# esp8266-somfy-switching.net
KiCad netlist of a schematic drawn in EAGLE
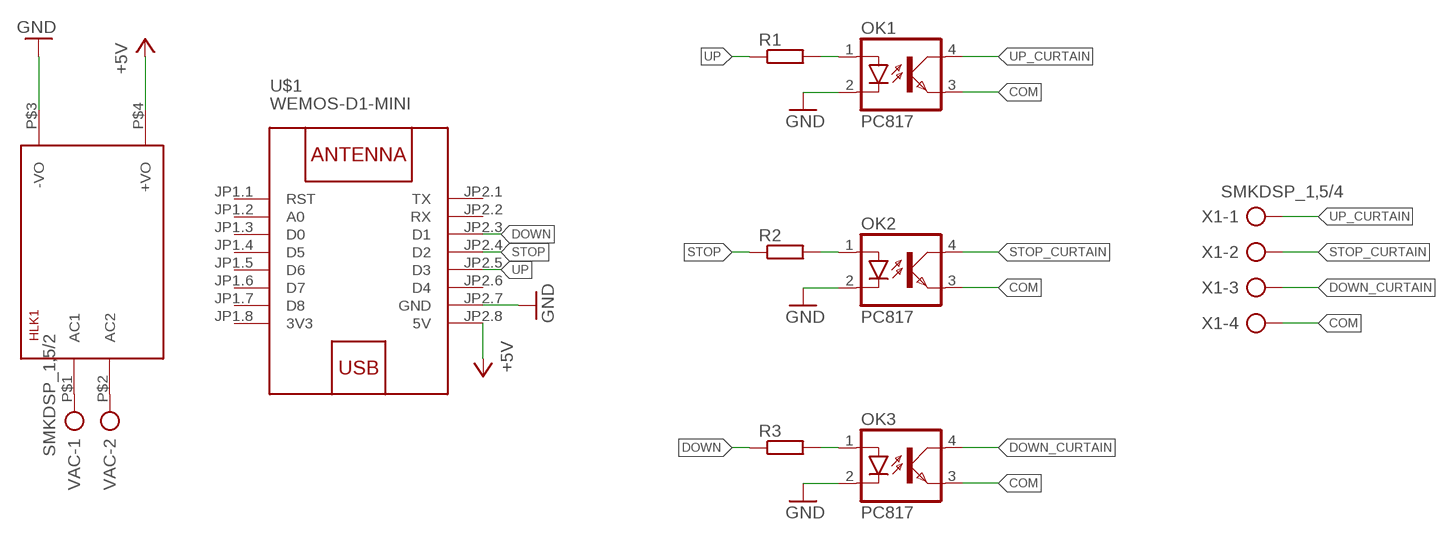
[diagram p0: schematic, sheet 1]

(export (version "E")
  (design (tool "Eeschema 10.0.6"))
  (components
    (comp (ref "HLK1")
      (value "HLK-PM013W")
      (footprint "eagle-import:HLK-PM01")
      (libsource (lib "eagle-import") (part "HLK-PM013W"))
    )
    (comp (ref "OK1")
      (value "PC817")
      (footprint "eagle-import:DIL04")
      (fields (field (name "MPN") "PC817X4J000F"))
      (libsource (lib "eagle-import") (part "PC817"))
    )
    (comp (ref "OK2")
      (value "PC817")
      (footprint "eagle-import:DIL04")
      (fields (field (name "MPN") "PC817X4J000F"))
      (libsource (lib "eagle-import") (part "PC817"))
    )
    (comp (ref "OK3")
      (value "PC817")
      (footprint "eagle-import:DIL04")
      (fields (field (name "MPN") "PC817X4J000F"))
      (libsource (lib "eagle-import") (part "PC817"))
    )
    (comp (ref "R1")
      (value "R-EU_0207/10")
      (footprint "eagle-import:0207_10")
      (libsource (lib "eagle-import") (part "R-EU_0207/10"))
    )
    (comp (ref "R2")
      (value "R-EU_0207/10")
      (footprint "eagle-import:0207_10")
      (libsource (lib "eagle-import") (part "R-EU_0207/10"))
    )
    (comp (ref "R3")
      (value "R-EU_0207/10")
      (footprint "eagle-import:0207_10")
      (libsource (lib "eagle-import") (part "R-EU_0207/10"))
    )
    (comp (ref "U$1")
      (value "WEMOS-D1-MINI")
      (footprint "eagle-import:WEMOS-D1-MINI")
      (libsource (lib "eagle-import") (part "WEMOS-D1-MINI"))
    )
    (comp (ref "VAC")
      (value "SMKDSP_1,5/2")
      (footprint "eagle-import:SMKDSP_1,5_2")
      (fields (field (name "MF") "FARNELL") (field (name "MPN") "1733570"))
      (libsource (lib "eagle-import") (part "SMKDSP_1,5/2"))
    )
    (comp (ref "X1")
      (value "SMKDSP_1,5/4")
      (footprint "eagle-import:SMKDSP_1,5_4")
      (fields (field (name "MF") "FARNELL") (field (name "MPN") "1733596"))
      (libsource (lib "eagle-import") (part "SMKDSP_1,5/4"))
    )
  )
  (nets
    (net (code "1") (name "+5V") (class "Default")
      (node (ref "HLK1") (pin "P$4") (pinfunction "+VO_P$4") (pintype "bidirectional"))
      (node (ref "U$1") (pin "JP2.8") (pinfunction "5V_JP2.8") (pintype "power_in"))
    )
    (net (code "2") (name "/3V3") (class "Default")
      (node (ref "U$1") (pin "JP1.8") (pinfunction "3V3_JP1.8") (pintype "power_in"))
    )
    (net (code "3") (name "COM") (class "Default")
      (node (ref "OK1") (pin "3") (pinfunction "EMIT_3") (pintype "passive"))
      (node (ref "OK2") (pin "3") (pinfunction "EMIT_3") (pintype "passive"))
      (node (ref "OK3") (pin "3") (pinfunction "EMIT_3") (pintype "passive"))
      (node (ref "X1") (pin "4") (pinfunction "KL_4") (pintype "passive"))
    )
    (net (code "4") (name "DOWN") (class "Default")
      (node (ref "R3") (pin "1") (pinfunction "1_1") (pintype "passive"))
      (node (ref "U$1") (pin "JP2.3") (pinfunction "D1_JP2.3") (pintype "bidirectional"))
    )
    (net (code "5") (name "DOWN_CURTAIN") (class "Default")
      (node (ref "OK3") (pin "4") (pinfunction "COL_4") (pintype "passive"))
      (node (ref "X1") (pin "3") (pinfunction "KL_3") (pintype "passive"))
    )
    (net (code "6") (name "GND") (class "Default")
      (node (ref "HLK1") (pin "P$3") (pinfunction "-VO_P$3") (pintype "bidirectional"))
      (node (ref "OK1") (pin "2") (pinfunction "C_2") (pintype "passive"))
      (node (ref "OK2") (pin "2") (pinfunction "C_2") (pintype "passive"))
      (node (ref "OK3") (pin "2") (pinfunction "C_2") (pintype "passive"))
      (node (ref "U$1") (pin "JP2.7") (pinfunction "GND_JP2.7") (pintype "power_in"))
    )
    (net (code "7") (name "Net-(HLK1-AC1)") (class "Default")
      (node (ref "HLK1") (pin "P$1") (pinfunction "AC1_P$1") (pintype "bidirectional"))
      (node (ref "VAC") (pin "1") (pinfunction "KL_1") (pintype "passive"))
    )
    (net (code "8") (name "Net-(HLK1-AC2)") (class "Default")
      (node (ref "HLK1") (pin "P$2") (pinfunction "AC2_P$2") (pintype "bidirectional"))
      (node (ref "VAC") (pin "2") (pinfunction "KL_2") (pintype "passive"))
    )
    (net (code "9") (name "Net-(OK1-A)") (class "Default")
      (node (ref "OK1") (pin "1") (pinfunction "A_1") (pintype "passive"))
      (node (ref "R1") (pin "2") (pinfunction "2_2") (pintype "passive"))
    )
    (net (code "10") (name "Net-(OK2-A)") (class "Default")
      (node (ref "OK2") (pin "1") (pinfunction "A_1") (pintype "passive"))
      (node (ref "R2") (pin "2") (pinfunction "2_2") (pintype "passive"))
    )
    (net (code "11") (name "Net-(OK3-A)") (class "Default")
      (node (ref "OK3") (pin "1") (pinfunction "A_1") (pintype "passive"))
      (node (ref "R3") (pin "2") (pinfunction "2_2") (pintype "passive"))
    )
    (net (code "12") (name "STOP") (class "Default")
      (node (ref "R2") (pin "1") (pinfunction "1_1") (pintype "passive"))
      (node (ref "U$1") (pin "JP2.4") (pinfunction "D2_JP2.4") (pintype "bidirectional"))
    )
    (net (code "13") (name "STOP_CURTAIN") (class "Default")
      (node (ref "OK2") (pin "4") (pinfunction "COL_4") (pintype "passive"))
      (node (ref "X1") (pin "2") (pinfunction "KL_2") (pintype "passive"))
    )
    (net (code "14") (name "UP") (class "Default")
      (node (ref "R1") (pin "1") (pinfunction "1_1") (pintype "passive"))
      (node (ref "U$1") (pin "JP2.5") (pinfunction "D3_JP2.5") (pintype "bidirectional"))
    )
    (net (code "15") (name "UP_CURTAIN") (class "Default")
      (node (ref "OK1") (pin "4") (pinfunction "COL_4") (pintype "passive"))
      (node (ref "X1") (pin "1") (pinfunction "KL_1") (pintype "passive"))
    )
    (net (code "16") (name "unconnected-(U$1-A0-PadJP1.2)") (class "Default")
      (node (ref "U$1") (pin "JP1.2") (pinfunction "A0_JP1.2") (pintype "bidirectional"))
    )
    (net (code "17") (name "unconnected-(U$1-D0-PadJP1.3)") (class "Default")
      (node (ref "U$1") (pin "JP1.3") (pinfunction "D0_JP1.3") (pintype "bidirectional"))
    )
    (net (code "18") (name "unconnected-(U$1-D4-PadJP2.6)") (class "Default")
      (node (ref "U$1") (pin "JP2.6") (pinfunction "D4_JP2.6") (pintype "bidirectional"))
    )
    (net (code "19") (name "unconnected-(U$1-D5-PadJP1.4)") (class "Default")
      (node (ref "U$1") (pin "JP1.4") (pinfunction "D5_JP1.4") (pintype "bidirectional"))
    )
    (net (code "20") (name "unconnected-(U$1-D6-PadJP1.5)") (class "Default")
      (node (ref "U$1") (pin "JP1.5") (pinfunction "D6_JP1.5") (pintype "bidirectional"))
    )
    (net (code "21") (name "unconnected-(U$1-D7-PadJP1.6)") (class "Default")
      (node (ref "U$1") (pin "JP1.6") (pinfunction "D7_JP1.6") (pintype "bidirectional"))
    )
    (net (code "22") (name "unconnected-(U$1-D8-PadJP1.7)") (class "Default")
      (node (ref "U$1") (pin "JP1.7") (pinfunction "D8_JP1.7") (pintype "bidirectional"))
    )
    (net (code "23") (name "unconnected-(U$1-RST-PadJP1.1)") (class "Default")
      (node (ref "U$1") (pin "JP1.1") (pinfunction "RST_JP1.1") (pintype "bidirectional"))
    )
    (net (code "24") (name "unconnected-(U$1-RX-PadJP2.2)") (class "Default")
      (node (ref "U$1") (pin "JP2.2") (pinfunction "RX_JP2.2") (pintype "bidirectional"))
    )
    (net (code "25") (name "unconnected-(U$1-TX-PadJP2.1)") (class "Default")
      (node (ref "U$1") (pin "JP2.1") (pinfunction "TX_JP2.1") (pintype "bidirectional"))
    )
  )
)
